# obc-v2_RTC-WDOG.net
KiCad netlist of a schematic drawn in Altium Designer
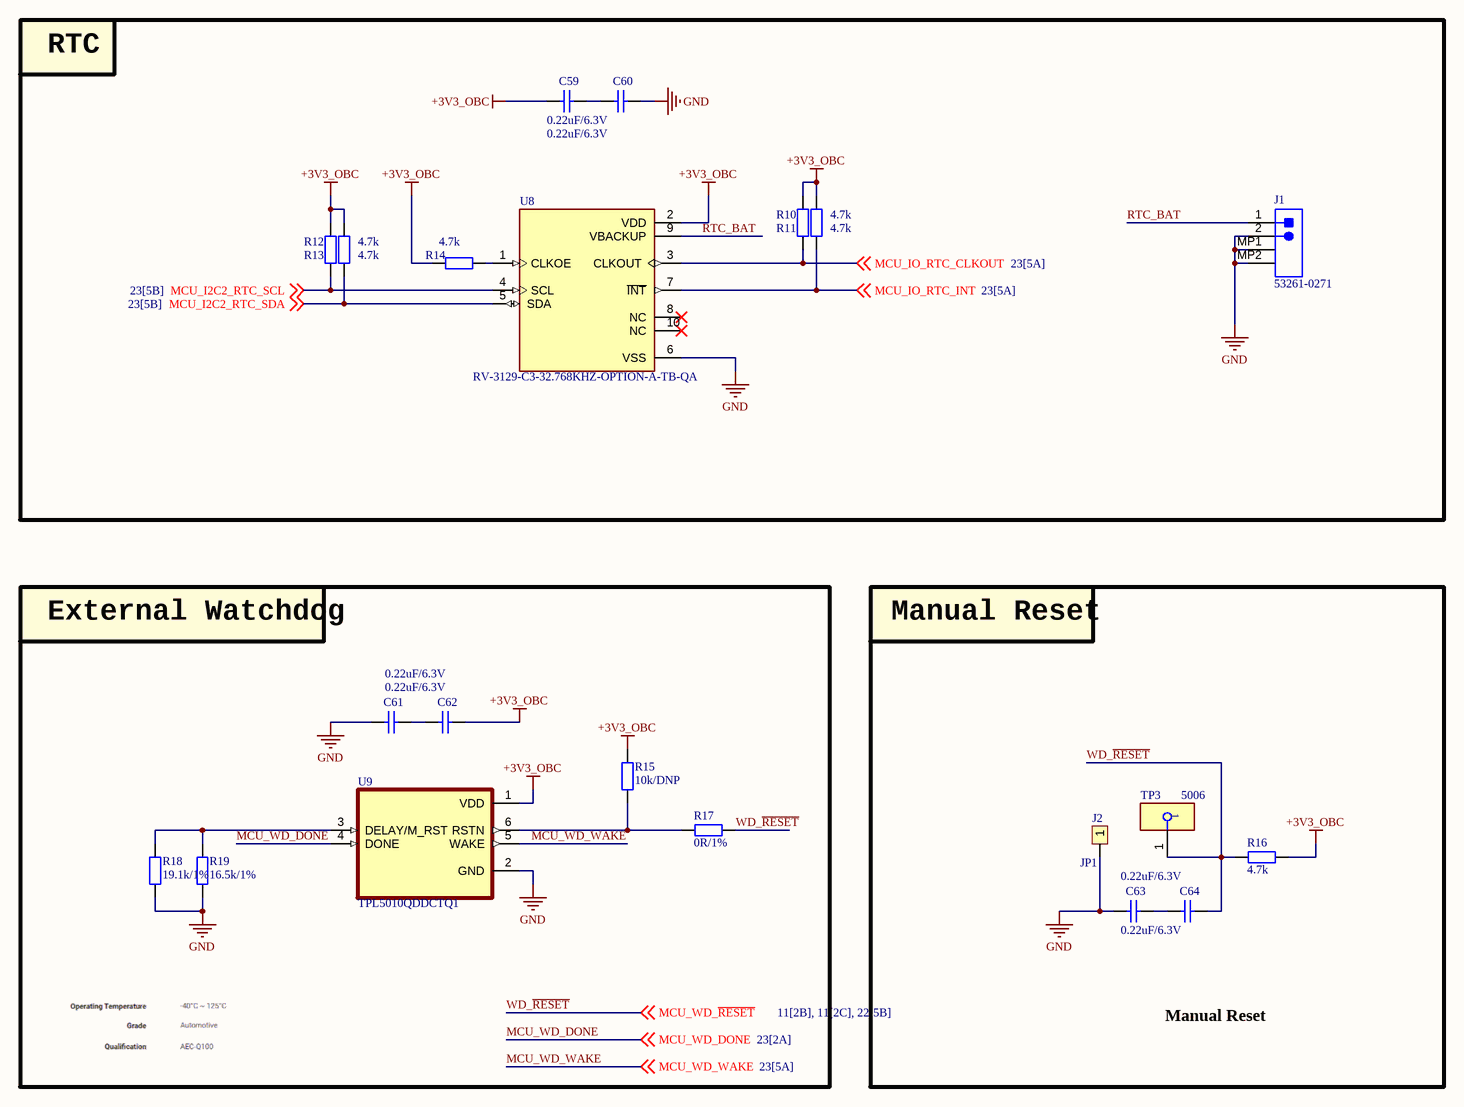
[diagram p0: obc-v2_RTC-WDOG.SchDoc]

(export (version "E")
  (design (tool "Eeschema 10.0.6"))
  (components
    (comp (ref "C59")
      (value "0.22uF/6.3V")
      (footprint "CAP_C_1005X60")
      (description "CAPC")
      (libsource (lib "Altium_Lib_by_KhueNguyenCreator") (part "Tu 0402 33nF 10V"))
    )
    (comp (ref "C60")
      (value "0.22uF/6.3V")
      (footprint "CAP_C_1005X60")
      (description "CAPC")
      (libsource (lib "Altium_Lib_by_KhueNguyenCreator") (part "Tu 0402 33nF 10V"))
    )
    (comp (ref "C61")
      (value "0.22uF/6.3V")
      (footprint "CAP_C_1005X60")
      (description "CAPC")
      (libsource (lib "Altium_Lib_by_KhueNguyenCreator") (part "Tu 0402 33nF 10V"))
    )
    (comp (ref "C62")
      (value "0.22uF/6.3V")
      (footprint "CAP_C_1005X60")
      (description "CAPC")
      (libsource (lib "Altium_Lib_by_KhueNguyenCreator") (part "Tu 0402 33nF 10V"))
    )
    (comp (ref "C63")
      (value "0.22uF/6.3V")
      (footprint "CAP_C_1005X60")
      (description "CAPC")
      (libsource (lib "Altium_Lib_by_KhueNguyenCreator") (part "Tu 0402 33nF 10V"))
    )
    (comp (ref "C64")
      (value "0.22uF/6.3V")
      (footprint "CAP_C_1005X60")
      (description "CAPC")
      (libsource (lib "Altium_Lib_by_KhueNguyenCreator") (part "Tu 0402 33nF 10V"))
    )
    (comp (ref "J1")
      (value "53261-0271")
      (footprint "MOLX-53261-0271_V")
      (description "PicoBlade(TM) Header, Right Angle, -40 to 85 degC, 2-Pin SMD, RoHS, Tape and Reel")
      (fields (field (name "MANUFACTURER") "Molex"))
      (libsource (lib "Altium Content Vault") (part "CN-1P-2M-R2"))
    )
    (comp (ref "J2")
      (value "JP1")
      (footprint "JP1-D1T")
      (description "WR-PHD 2.54 mm Angled Socket Header")
      (fields
        (field (name "MANUFACTURER") "Würth Elektronik eiSos GmbH")
        (field (name "PARTNO") "613002143121")
        (field (name "CREATED BY") "Karrer Zheng")
      )
      (libsource (lib "TechMT.VN_Lib_Project v2") (part "JP1"))
    )
    (comp (ref "R10")
      (value "4.7k")
      (footprint "RES_C_1608X60")
      (description "RES")
      (libsource (lib "Altium_Lib_by_KhueNguyenCreator") (part "Tro 0603 1% 10k"))
    )
    (comp (ref "R11")
      (value "4.7k")
      (footprint "RES_C_1608X60")
      (description "RES")
      (libsource (lib "Altium_Lib_by_KhueNguyenCreator") (part "Tro 0603 1% 10k"))
    )
    (comp (ref "R12")
      (value "4.7k")
      (footprint "RES_C_1608X60")
      (description "RES")
      (libsource (lib "Altium_Lib_by_KhueNguyenCreator") (part "Tro 0603 1% 10k"))
    )
    (comp (ref "R13")
      (value "4.7k")
      (footprint "RES_C_1608X60")
      (description "RES")
      (libsource (lib "Altium_Lib_by_KhueNguyenCreator") (part "Tro 0603 1% 10k"))
    )
    (comp (ref "R14")
      (value "4.7k")
      (footprint "RES_C_1608X60")
      (description "RES")
      (libsource (lib "Altium_Lib_by_KhueNguyenCreator") (part "Tro 0603 1% 10k"))
    )
    (comp (ref "R15")
      (value "10k/DNP")
      (footprint "RES_C_1608X60")
      (description "RES SMD 10K OHM 1% 1/10W 0603, P/N: ERJ-3EKF1002V")
      (libsource (lib "Altium_Lib_by_KhueNguyenCreator") (part "Tro 0603 1% 10k"))
    )
    (comp (ref "R16")
      (value "4.7k")
      (footprint "RES_C_1608X60")
      (description "RES")
      (libsource (lib "Altium_Lib_by_KhueNguyenCreator") (part "Tro 0603 1% 10k"))
    )
    (comp (ref "R17")
      (value "0R/1%")
      (footprint "RES_C_1608X60")
      (description "RES")
      (libsource (lib "Altium_Lib_by_KhueNguyenCreator") (part "Tro 0603 1% 10k"))
    )
    (comp (ref "R18")
      (value "19.1k/1%")
      (footprint "RES_C_1608X60")
      (description "RES SMD 19.1K OHM 1% 1/10W 0603, P/N: ERJ-3EKF1912V")
      (libsource (lib "Altium_Lib_by_KhueNguyenCreator") (part "Tro 0603 1% 10k"))
    )
    (comp (ref "R19")
      (value "16.5k/1%")
      (footprint "RES_C_1608X60")
      (description "RES SMD 16.5K OHM 1% 1/10W 0603, P/N: ERJ-3EKF1652V")
      (libsource (lib "Altium_Lib_by_KhueNguyenCreator") (part "Tro 0603 1% 10k"))
    )
    (comp (ref "TP3")
      (value "5006")
      (footprint "FP-5006-MFG")
      (description "PC TEST POINT COMPACT BLACK")
      (libsource (lib "Altium Content Vault") (part "98815daf2f2c152b0c43f5ab9800df6"))
    )
    (comp (ref "U8")
      (value "RV-3129-C3-32.768KHZ-OPTION-A-TB-QA")
      (footprint "IC_RV-3129-C3_32.768KHZ_OPTION_A_TB_QA")
      (description "Real-Time Clock Module, Temperature compensated, in 2.5 x 3.7 mm package")
      (fields (field (name "MF") "Micro Crystal") (field (name "MP") "RV-3129-C3 32.768KHZ OPTION A TB QA"))
      (libsource (lib "RV-3129-C3_32.768KHZ_OPTION_A_TB_QA") (part "RV-3129-C3_32.768KHZ_OPTION_A_TB_QA"))
    )
    (comp (ref "U9")
      (value "TPL5010QDDCTQ1")
      (footprint "SOT95P280X110-6N")
      (libsource (lib "TPL5010QDDCTQ1") (part "TPL5010QDDCTQ1"))
    )
  )
  (nets
    (net (code "1") (name "+3V3_OBC") (class "Default")
      (node (ref "C59") (pin "2") (pinfunction "2_2") (pintype "passive"))
      (node (ref "C62") (pin "1") (pinfunction "1_1") (pintype "passive"))
      (node (ref "R10") (pin "2") (pinfunction "2_2") (pintype "passive"))
      (node (ref "R11") (pin "2") (pinfunction "2_2") (pintype "passive"))
      (node (ref "R12") (pin "2") (pinfunction "2_2") (pintype "passive"))
      (node (ref "R13") (pin "2") (pinfunction "2_2") (pintype "passive"))
      (node (ref "R14") (pin "2") (pinfunction "2_2") (pintype "passive"))
      (node (ref "R15") (pin "2") (pinfunction "2_2") (pintype "passive"))
      (node (ref "R16") (pin "2") (pinfunction "2_2") (pintype "passive"))
      (node (ref "U8") (pin "2") (pinfunction "VDD_2") (pintype "power_in"))
      (node (ref "U9") (pin "1") (pinfunction "VDD_1") (pintype "power_in"))
    )
    (net (code "2") (name "/RTC_BAT") (class "Default")
      (node (ref "J1") (pin "1") (pinfunction "1_1") (pintype "passive"))
      (node (ref "U8") (pin "9") (pinfunction "VBACKUP_9") (pintype "power_in"))
    )
    (net (code "3") (name "GND") (class "Default")
      (node (ref "C60") (pin "1") (pinfunction "1_1") (pintype "passive"))
      (node (ref "C61") (pin "2") (pinfunction "2_2") (pintype "passive"))
      (node (ref "C63") (pin "2") (pinfunction "2_2") (pintype "passive"))
      (node (ref "J1") (pin "2") (pinfunction "2_2") (pintype "passive"))
      (node (ref "J1") (pin "MP1") (pinfunction "MP1_MP1") (pintype "passive"))
      (node (ref "J1") (pin "MP2") (pinfunction "MP2_MP2") (pintype "passive"))
      (node (ref "J2") (pin "1") (pinfunction "1_1") (pintype "passive"))
      (node (ref "R18") (pin "1") (pinfunction "1_1") (pintype "passive"))
      (node (ref "R19") (pin "1") (pinfunction "1_1") (pintype "passive"))
      (node (ref "U8") (pin "6") (pinfunction "VSS_6") (pintype "power_in"))
      (node (ref "U9") (pin "2") (pinfunction "GND_2") (pintype "power_in"))
    )
    (net (code "4") (name "MCU_I2C2_RTC_SCL") (class "Default")
      (node (ref "R13") (pin "1") (pinfunction "1_1") (pintype "passive"))
      (node (ref "U8") (pin "4") (pinfunction "SCL_4") (pintype "input"))
    )
    (net (code "5") (name "MCU_I2C2_RTC_SDA") (class "Default")
      (node (ref "R12") (pin "1") (pinfunction "1_1") (pintype "passive"))
      (node (ref "U8") (pin "5") (pinfunction "SDA_5") (pintype "bidirectional"))
    )
    (net (code "6") (name "MCU_IO_RTC_CLKOUT") (class "Default")
      (node (ref "R11") (pin "1") (pinfunction "1_1") (pintype "passive"))
      (node (ref "U8") (pin "3") (pinfunction "CLKOUT_3") (pintype "output"))
    )
    (net (code "7") (name "MCU_IO_RTC_INT") (class "Default")
      (node (ref "R10") (pin "1") (pinfunction "1_1") (pintype "passive"))
      (node (ref "U8") (pin "7") (pinfunction "~{INT}_7") (pintype "output"))
    )
    (net (code "8") (name "MCU_WD_DONE") (class "Default")
      (node (ref "U9") (pin "4") (pinfunction "DONE_4") (pintype "input"))
    )
    (net (code "9") (name "MCU_WD_WAKE") (class "Default")
      (node (ref "U9") (pin "5") (pinfunction "WAKE_5") (pintype "output"))
    )
    (net (code "10") (name "MCU_WD_~{RESET}") (class "Default")
      (node (ref "C64") (pin "1") (pinfunction "1_1") (pintype "passive"))
      (node (ref "R16") (pin "1") (pinfunction "1_1") (pintype "passive"))
      (node (ref "R17") (pin "1") (pinfunction "1_1") (pintype "passive"))
      (node (ref "TP3") (pin "1") (pinfunction "1_1") (pintype "passive"))
    )
    (net (code "11") (name "Net-(C59-Pad1)") (class "Default")
      (node (ref "C59") (pin "1") (pinfunction "1_1") (pintype "passive"))
      (node (ref "C60") (pin "2") (pinfunction "2_2") (pintype "passive"))
    )
    (net (code "12") (name "Net-(C61-Pad1)") (class "Default")
      (node (ref "C61") (pin "1") (pinfunction "1_1") (pintype "passive"))
      (node (ref "C62") (pin "2") (pinfunction "2_2") (pintype "passive"))
    )
    (net (code "13") (name "Net-(C63-Pad1)") (class "Default")
      (node (ref "C63") (pin "1") (pinfunction "1_1") (pintype "passive"))
      (node (ref "C64") (pin "2") (pinfunction "2_2") (pintype "passive"))
    )
    (net (code "14") (name "Net-(U8-CLKOE)") (class "Default")
      (node (ref "R14") (pin "1") (pinfunction "1_1") (pintype "passive"))
      (node (ref "U8") (pin "1") (pinfunction "CLKOE_1") (pintype "input"))
    )
    (net (code "15") (name "Net-(U9-DELAY{slash}M_RST)") (class "Default")
      (node (ref "R18") (pin "2") (pinfunction "2_2") (pintype "passive"))
      (node (ref "R19") (pin "2") (pinfunction "2_2") (pintype "passive"))
      (node (ref "U9") (pin "3") (pinfunction "DELAY/M_RST_3") (pintype "input"))
    )
    (net (code "16") (name "Net-(U9-RSTN)") (class "Default")
      (node (ref "R15") (pin "1") (pinfunction "1_1") (pintype "passive"))
      (node (ref "R17") (pin "2") (pinfunction "2_2") (pintype "passive"))
      (node (ref "U9") (pin "6") (pinfunction "RSTN_6") (pintype "output"))
    )
    (net (code "17") (name "unconnected-(U8-NC-Pad8)") (class "Default")
      (node (ref "U8") (pin "8") (pinfunction "NC_8") (pintype "passive+no_connect"))
    )
    (net (code "18") (name "unconnected-(U8-NC-Pad10)") (class "Default")
      (node (ref "U8") (pin "10") (pinfunction "NC_10") (pintype "passive+no_connect"))
    )
  )
)
